# Humidifier.net
KiCad netlist of a schematic drawn in Altium Designer
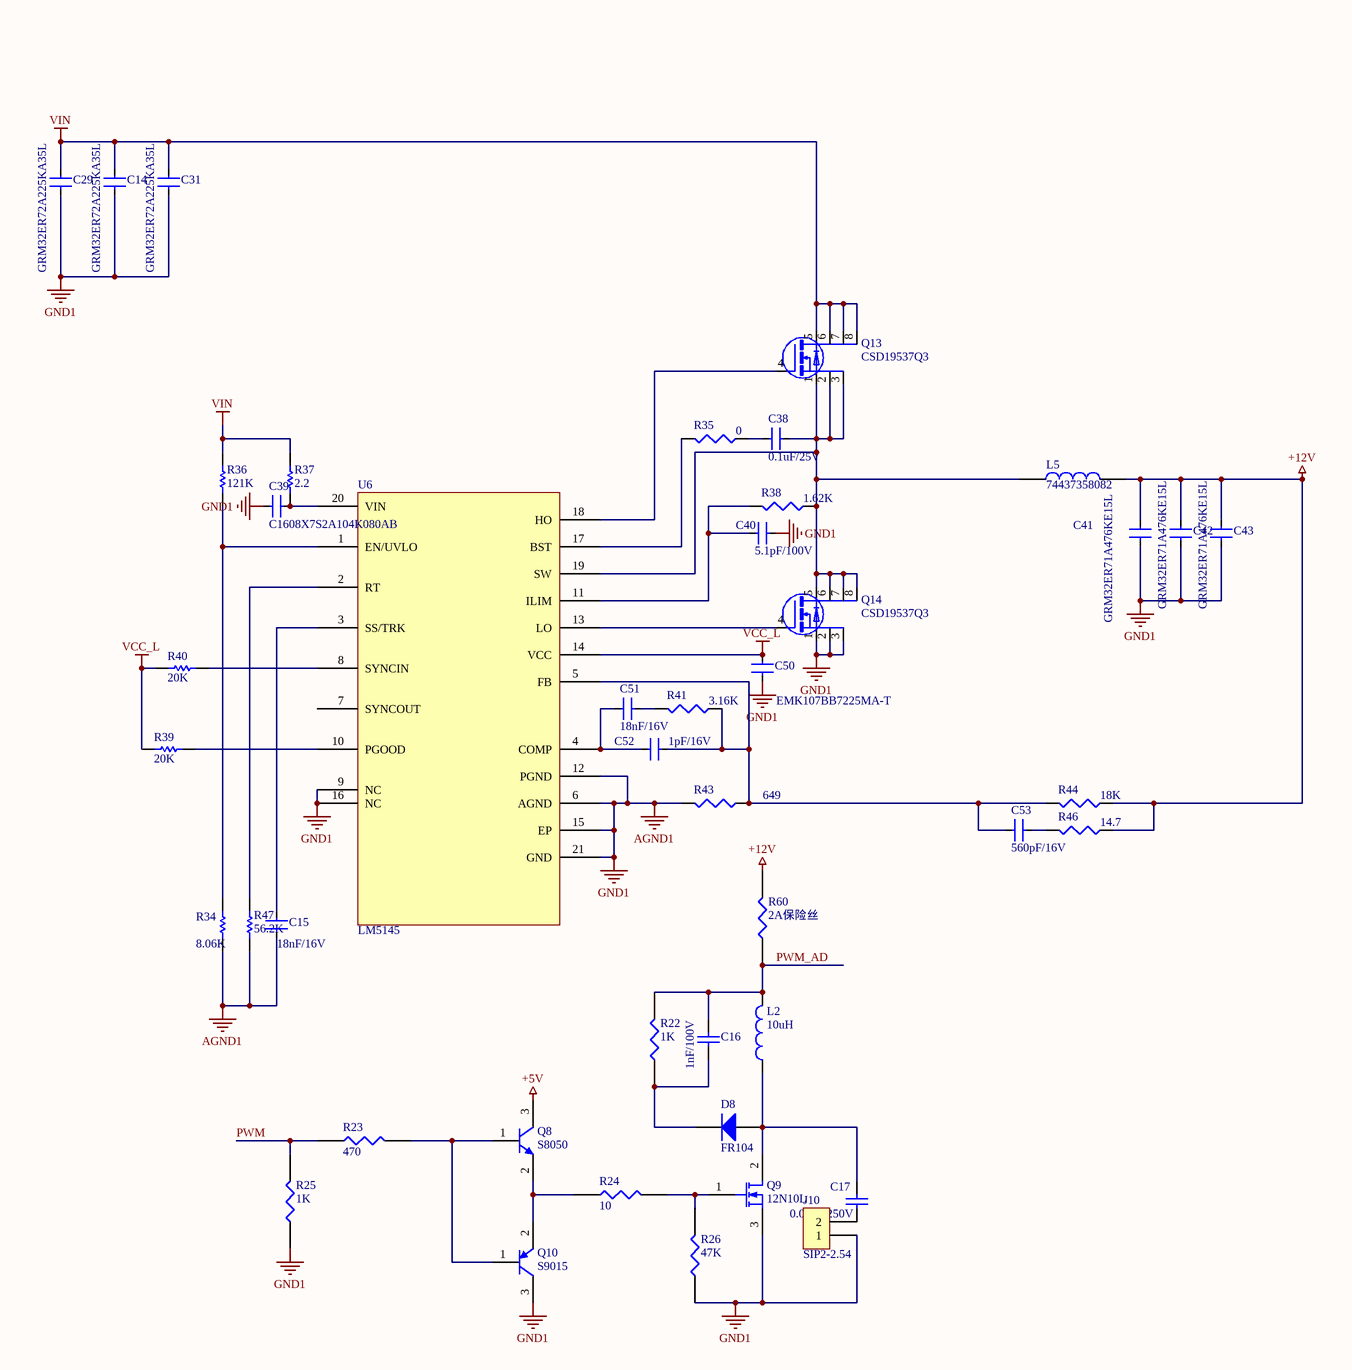
[diagram p0: Humidifier.SchDoc]

(export (version "E")
  (design (tool "Eeschema 10.0.6"))
  (components
    (comp (ref "C14")
      (value "GRM32ER72A225KA35L")
      (footprint "1210C")
      (description "CCX85-103")
      (libsource (lib "无极性电容") (part "0.01UF"))
    )
    (comp (ref "C15")
      (value "18nF/16V")
      (footprint "0603C")
      (description "CCX85-103")
      (libsource (lib "无极性电容") (part "0.01UF"))
    )
    (comp (ref "C16")
      (value "1nF/100V")
      (footprint "CAP_5MM")
      (description "Capacitor")
      (fields (field (name "PUBLISHER") "Altium Limited"))
      (libsource (lib "Miscellaneous Devices") (part "Cap"))
    )
    (comp (ref "C17")
      (value "0.047F/250V")
      (footprint "CAP_5MM")
      (description "Capacitor")
      (fields (field (name "PUBLISHER") "Altium Limited"))
      (libsource (lib "Miscellaneous Devices") (part "Cap"))
    )
    (comp (ref "C29")
      (value "GRM32ER72A225KA35L")
      (footprint "1210C")
      (description "CCX85-103")
      (libsource (lib "无极性电容") (part "0.01UF"))
    )
    (comp (ref "C31")
      (value "GRM32ER72A225KA35L")
      (footprint "1210C")
      (description "CCX85-103")
      (libsource (lib "无极性电容") (part "0.01UF"))
    )
    (comp (ref "C38")
      (value "0.1uF/25V")
      (footprint "0603C")
      (description "CCX85-103")
      (libsource (lib "无极性电容") (part "0.01UF"))
    )
    (comp (ref "C39")
      (value "C1608X7S2A104K080AB")
      (footprint "0603C")
      (description "CCX85-103")
      (libsource (lib "无极性电容") (part "0.01UF"))
    )
    (comp (ref "C40")
      (value "5.1pF/100V")
      (footprint "0603C")
      (description "CCX85-103")
      (libsource (lib "无极性电容") (part "0.01UF"))
    )
    (comp (ref "C41")
      (value "GRM32ER71A476KE15L")
      (footprint "1210C")
      (description "CCX85-103")
      (libsource (lib "无极性电容") (part "0.01UF"))
    )
    (comp (ref "C42")
      (value "GRM32ER71A476KE15L")
      (footprint "1210C")
      (description "CCX85-103")
      (libsource (lib "无极性电容") (part "0.01UF"))
    )
    (comp (ref "C43")
      (value "GRM32ER71A476KE15L")
      (footprint "1210C")
      (description "CCX85-103")
      (libsource (lib "无极性电容") (part "0.01UF"))
    )
    (comp (ref "C50")
      (value "EMK107BB7225MA-T")
      (footprint "0603C")
      (description "CCX85-103")
      (libsource (lib "无极性电容") (part "0.01UF"))
    )
    (comp (ref "C51")
      (value "18nF/16V")
      (footprint "0603C")
      (description "CCX85-103")
      (libsource (lib "无极性电容") (part "0.01UF"))
    )
    (comp (ref "C52")
      (value "1pF/16V")
      (footprint "0603C")
      (description "CCX85-103")
      (libsource (lib "无极性电容") (part "0.01UF"))
    )
    (comp (ref "C53")
      (value "560pF/16V")
      (footprint "0603C")
      (description "CCX85-103")
      (libsource (lib "无极性电容") (part "0.01UF"))
    )
    (comp (ref "D8")
      (value "FR104")
      (footprint "SMA")
      (description "Default Diode")
      (fields (field (name "PUBLISHER") "Altium Limited"))
      (libsource (lib "SM") (part "Diode_2"))
    )
    (comp (ref "J10")
      (value "SIP2-2.54")
      (footprint "SIP-2L")
      (description "CN-SIP2-2.54")
      (libsource (lib "接插件") (part "SIP2-2.54"))
    )
    (comp (ref "L2")
      (value "10uH")
      (footprint "6*8")
      (description "Inductor")
      (fields (field (name "PUBLISHER") "Altium Limited"))
      (libsource (lib "Miscellaneous Devices") (part "Inductor"))
    )
    (comp (ref "L5") (value "74437358082") (footprint "SRP1270-2R2M") (libsource (lib "*") (part "INDUCTOR")))
    (comp (ref "Q8")
      (value "S8050")
      (footprint "SOT23-3")
      (description "NPN Bipolar Transistor")
      (fields (field (name "PUBLISHER") "Altium Limited"))
      (libsource (lib "Miscellaneous Devices") (part "NPN"))
    )
    (comp (ref "Q9")
      (value "12N10L")
      (footprint "TO230P973X238-3N")
      (description "N-Channel MOSFET")
      (fields (field (name "PUBLISHER") "Altium Limited"))
      (libsource (lib "Miscellaneous Devices") (part "MOSFET-N"))
    )
    (comp (ref "Q10")
      (value "S9015")
      (footprint "SOT23-3")
      (description "PNP Bipolar Transistor")
      (fields (field (name "PUBLISHER") "Altium Limited"))
      (libsource (lib "Miscellaneous Devices") (part "PNP"))
    )
    (comp (ref "Q13")
      (value "CSD19537Q3")
      (footprint "PowerPAK SO-8")
      (description "Si4004DY")
      (libsource (lib "Schlib_20110825") (part "Si4004DY"))
    )
    (comp (ref "Q14")
      (value "CSD19537Q3")
      (footprint "PowerPAK SO-8")
      (description "Si4004DY")
      (libsource (lib "Schlib_20110825") (part "Si4004DY"))
    )
    (comp (ref "R22") (value "1K") (footprint "0805R") (libsource (lib "其他电阻") (part "RES1")))
    (comp (ref "R23") (value "470") (footprint "0805R") (libsource (lib "其他电阻") (part "RES1")))
    (comp (ref "R24") (value "10") (footprint "0805R") (libsource (lib "其他电阻") (part "RES1")))
    (comp (ref "R25") (value "1K") (footprint "0805R") (libsource (lib "其他电阻") (part "RES1")))
    (comp (ref "R26") (value "47K") (footprint "0805R") (libsource (lib "其他电阻") (part "RES1")))
    (comp (ref "R34")
      (value "8.06K")
      (footprint "0603R")
      (description "Semiconductor Resistor")
      (fields (field (name "PUBLISHER") "Altium Limited"))
      (libsource (lib "Miscellaneous Devices") (part "Res Semi"))
    )
    (comp (ref "R35")
      (value "0")
      (footprint "0603R")
      (description "Resistor")
      (fields (field (name "PUBLISHER") "Altium Limited"))
      (libsource (lib "SM") (part "Res3"))
    )
    (comp (ref "R36")
      (value "121K")
      (footprint "0805R")
      (description "Semiconductor Resistor")
      (fields (field (name "PUBLISHER") "Altium Limited"))
      (libsource (lib "Miscellaneous Devices") (part "Res Semi"))
    )
    (comp (ref "R37")
      (value "2.2")
      (footprint "0603R")
      (description "Semiconductor Resistor")
      (fields (field (name "PUBLISHER") "Altium Limited"))
      (libsource (lib "Miscellaneous Devices") (part "Res Semi"))
    )
    (comp (ref "R38")
      (value "1.62K")
      (footprint "0603R")
      (description "Resistor")
      (fields (field (name "PUBLISHER") "Altium Limited"))
      (libsource (lib "SM") (part "Res3"))
    )
    (comp (ref "R39")
      (value "20K")
      (footprint "0603R")
      (description "Semiconductor Resistor")
      (fields (field (name "PUBLISHER") "Altium Limited"))
      (libsource (lib "Miscellaneous Devices") (part "Res Semi"))
    )
    (comp (ref "R40")
      (value "20K")
      (footprint "0603R")
      (description "Semiconductor Resistor")
      (fields (field (name "PUBLISHER") "Altium Limited"))
      (libsource (lib "Miscellaneous Devices") (part "Res Semi"))
    )
    (comp (ref "R41")
      (value "3.16K")
      (footprint "0603R")
      (description "Resistor")
      (fields (field (name "PUBLISHER") "Altium Limited"))
      (libsource (lib "SM") (part "Res3"))
    )
    (comp (ref "R43")
      (value "649")
      (footprint "0603R")
      (description "Resistor")
      (fields (field (name "PUBLISHER") "Altium Limited"))
      (libsource (lib "SM") (part "Res3"))
    )
    (comp (ref "R44")
      (value "18K")
      (footprint "0603R")
      (description "Resistor")
      (fields (field (name "PUBLISHER") "Altium Limited"))
      (libsource (lib "SM") (part "Res3"))
    )
    (comp (ref "R46")
      (value "14.7")
      (footprint "0603R")
      (description "Resistor")
      (fields (field (name "PUBLISHER") "Altium Limited"))
      (libsource (lib "SM") (part "Res3"))
    )
    (comp (ref "R47")
      (value "56.2K")
      (footprint "0603R")
      (description "Semiconductor Resistor")
      (fields (field (name "PUBLISHER") "Altium Limited"))
      (libsource (lib "Miscellaneous Devices") (part "Res Semi"))
    )
    (comp (ref "R60") (value "2A保险丝") (footprint "0805R") (libsource (lib "其他电阻") (part "RES1")))
    (comp (ref "U6")
      (value "LM5145")
      (footprint "QFN050P600-8N")
      (libsource (lib "Schlib_20110825") (part "LM5145"))
    )
  )
  (nets
    (net (code "1") (name "+5V") (class "Default")
      (node (ref "Q8") (pin "3") (pinfunction "C_3") (pintype "passive"))
    )
    (net (code "2") (name "+12V") (class "Default")
      (node (ref "C41") (pin "1") (pinfunction "1_1") (pintype "passive"))
      (node (ref "C42") (pin "1") (pinfunction "1_1") (pintype "passive"))
      (node (ref "C43") (pin "1") (pinfunction "1_1") (pintype "passive"))
      (node (ref "L5") (pin "2") (pinfunction "2_2") (pintype "passive"))
      (node (ref "R44") (pin "1") (pinfunction "1_1") (pintype "passive"))
      (node (ref "R46") (pin "1") (pinfunction "1_1") (pintype "passive"))
      (node (ref "R60") (pin "2") (pinfunction "2_2") (pintype "passive"))
    )
    (net (code "3") (name "/PWM") (class "Default")
      (node (ref "R23") (pin "1") (pinfunction "1_1") (pintype "passive"))
      (node (ref "R25") (pin "2") (pinfunction "2_2") (pintype "passive"))
    )
    (net (code "4") (name "/PWM_AD") (class "Default")
      (node (ref "C16") (pin "2") (pinfunction "2_2") (pintype "passive"))
      (node (ref "L2") (pin "2") (pinfunction "2_2") (pintype "passive"))
      (node (ref "R22") (pin "2") (pinfunction "2_2") (pintype "passive"))
      (node (ref "R60") (pin "1") (pinfunction "1_1") (pintype "passive"))
    )
    (net (code "5") (name "AGND1") (class "Default")
      (node (ref "C14") (pin "2") (pinfunction "2_2") (pintype "passive"))
      (node (ref "C15") (pin "2") (pinfunction "2_2") (pintype "passive"))
      (node (ref "C29") (pin "2") (pinfunction "2_2") (pintype "passive"))
      (node (ref "C31") (pin "2") (pinfunction "2_2") (pintype "passive"))
      (node (ref "C39") (pin "1") (pinfunction "1_1") (pintype "passive"))
      (node (ref "C40") (pin "1") (pinfunction "1_1") (pintype "passive"))
      (node (ref "C41") (pin "2") (pinfunction "2_2") (pintype "passive"))
      (node (ref "C42") (pin "2") (pinfunction "2_2") (pintype "passive"))
      (node (ref "C43") (pin "2") (pinfunction "2_2") (pintype "passive"))
      (node (ref "C50") (pin "2") (pinfunction "2_2") (pintype "passive"))
      (node (ref "J10") (pin "1") (pinfunction "1_1") (pintype "passive"))
      (node (ref "Q10") (pin "3") (pinfunction "C_3") (pintype "passive"))
      (node (ref "Q14") (pin "1") (pinfunction "S_1") (pintype "passive"))
      (node (ref "Q14") (pin "2") (pinfunction "S_2") (pintype "passive"))
      (node (ref "Q14") (pin "3") (pinfunction "S_3") (pintype "passive"))
      (node (ref "Q9") (pin "3") (pinfunction "S_3") (pintype "passive"))
      (node (ref "R25") (pin "1") (pinfunction "1_1") (pintype "passive"))
      (node (ref "R26") (pin "1") (pinfunction "1_1") (pintype "passive"))
      (node (ref "R34") (pin "1") (pinfunction "1_1") (pintype "passive"))
      (node (ref "R43") (pin "2") (pinfunction "2_2") (pintype "passive"))
      (node (ref "R47") (pin "1") (pinfunction "1_1") (pintype "passive"))
      (node (ref "U6") (pin "12") (pinfunction "PGND_12") (pintype "passive"))
      (node (ref "U6") (pin "15") (pinfunction "EP_15") (pintype "passive"))
      (node (ref "U6") (pin "16") (pinfunction "NC_16") (pintype "passive"))
      (node (ref "U6") (pin "21") (pinfunction "GND_21") (pintype "passive"))
      (node (ref "U6") (pin "6") (pinfunction "AGND_6") (pintype "passive"))
      (node (ref "U6") (pin "9") (pinfunction "NC_9") (pintype "passive"))
    )
    (net (code "6") (name "Net-(C17-Pad1)") (class "Default")
      (node (ref "C17") (pin "1") (pinfunction "1_1") (pintype "passive"))
      (node (ref "J10") (pin "2") (pinfunction "2_2") (pintype "passive"))
    )
    (net (code "7") (name "Net-(C38-Pad1)") (class "Default")
      (node (ref "C38") (pin "1") (pinfunction "1_1") (pintype "passive"))
      (node (ref "R35") (pin "1") (pinfunction "1_1") (pintype "passive"))
    )
    (net (code "8") (name "Net-(C51-Pad2)") (class "Default")
      (node (ref "C51") (pin "2") (pinfunction "2_2") (pintype "passive"))
      (node (ref "R41") (pin "2") (pinfunction "2_2") (pintype "passive"))
    )
    (net (code "9") (name "Net-(C53-Pad2)") (class "Default")
      (node (ref "C53") (pin "2") (pinfunction "2_2") (pintype "passive"))
      (node (ref "R46") (pin "2") (pinfunction "2_2") (pintype "passive"))
    )
    (net (code "10") (name "Net-(D8-A)") (class "Default")
      (node (ref "C17") (pin "2") (pinfunction "2_2") (pintype "passive"))
      (node (ref "D8") (pin "1") (pinfunction "A_1") (pintype "passive"))
      (node (ref "L2") (pin "1") (pinfunction "1_1") (pintype "passive"))
      (node (ref "Q9") (pin "2") (pinfunction "D_2") (pintype "passive"))
    )
    (net (code "11") (name "Net-(D8-K)") (class "Default")
      (node (ref "C16") (pin "1") (pinfunction "1_1") (pintype "passive"))
      (node (ref "D8") (pin "2") (pinfunction "K_2") (pintype "passive"))
      (node (ref "R22") (pin "1") (pinfunction "1_1") (pintype "passive"))
    )
    (net (code "12") (name "Net-(Q9-G)") (class "Default")
      (node (ref "Q9") (pin "1") (pinfunction "G_1") (pintype "passive"))
      (node (ref "R24") (pin "2") (pinfunction "2_2") (pintype "passive"))
      (node (ref "R26") (pin "2") (pinfunction "2_2") (pintype "passive"))
    )
    (net (code "13") (name "Net-(Q10-B)") (class "Default")
      (node (ref "Q10") (pin "1") (pinfunction "B_1") (pintype "passive"))
      (node (ref "Q8") (pin "1") (pinfunction "B_1") (pintype "passive"))
      (node (ref "R23") (pin "2") (pinfunction "2_2") (pintype "passive"))
    )
    (net (code "14") (name "Net-(Q10-E)") (class "Default")
      (node (ref "Q10") (pin "2") (pinfunction "E_2") (pintype "passive"))
      (node (ref "Q8") (pin "2") (pinfunction "E_2") (pintype "passive"))
      (node (ref "R24") (pin "1") (pinfunction "1_1") (pintype "passive"))
    )
    (net (code "15") (name "Net-(Q13-G)") (class "Default")
      (node (ref "Q13") (pin "4") (pinfunction "G_4") (pintype "passive"))
      (node (ref "U6") (pin "18") (pinfunction "HO_18") (pintype "passive"))
    )
    (net (code "16") (name "Net-(Q14-G)") (class "Default")
      (node (ref "Q14") (pin "4") (pinfunction "G_4") (pintype "passive"))
      (node (ref "U6") (pin "13") (pinfunction "LO_13") (pintype "passive"))
    )
    (net (code "17") (name "Net-(U6-BST)") (class "Default")
      (node (ref "R35") (pin "2") (pinfunction "2_2") (pintype "passive"))
      (node (ref "U6") (pin "17") (pinfunction "BST_17") (pintype "passive"))
    )
    (net (code "18") (name "Net-(U6-COMP)") (class "Default")
      (node (ref "C51") (pin "1") (pinfunction "1_1") (pintype "passive"))
      (node (ref "C52") (pin "1") (pinfunction "1_1") (pintype "passive"))
      (node (ref "U6") (pin "4") (pinfunction "COMP_4") (pintype "passive"))
    )
    (net (code "19") (name "Net-(U6-EN{slash}UVLO)") (class "Default")
      (node (ref "R34") (pin "2") (pinfunction "2_2") (pintype "passive"))
      (node (ref "R36") (pin "1") (pinfunction "1_1") (pintype "passive"))
      (node (ref "U6") (pin "1") (pinfunction "EN/UVLO_1") (pintype "passive"))
    )
    (net (code "20") (name "Net-(U6-FB)") (class "Default")
      (node (ref "C52") (pin "2") (pinfunction "2_2") (pintype "passive"))
      (node (ref "C53") (pin "1") (pinfunction "1_1") (pintype "passive"))
      (node (ref "R41") (pin "1") (pinfunction "1_1") (pintype "passive"))
      (node (ref "R43") (pin "1") (pinfunction "1_1") (pintype "passive"))
      (node (ref "R44") (pin "2") (pinfunction "2_2") (pintype "passive"))
      (node (ref "U6") (pin "5") (pinfunction "FB_5") (pintype "passive"))
    )
    (net (code "21") (name "Net-(U6-ILIM)") (class "Default")
      (node (ref "C40") (pin "2") (pinfunction "2_2") (pintype "passive"))
      (node (ref "R38") (pin "2") (pinfunction "2_2") (pintype "passive"))
      (node (ref "U6") (pin "11") (pinfunction "ILIM_11") (pintype "passive"))
    )
    (net (code "22") (name "Net-(U6-PGOOD)") (class "Default")
      (node (ref "R39") (pin "1") (pinfunction "1_1") (pintype "passive"))
      (node (ref "U6") (pin "10") (pinfunction "PGOOD_10") (pintype "passive"))
    )
    (net (code "23") (name "Net-(U6-RT)") (class "Default")
      (node (ref "R47") (pin "2") (pinfunction "2_2") (pintype "passive"))
      (node (ref "U6") (pin "2") (pinfunction "RT_2") (pintype "passive"))
    )
    (net (code "24") (name "Net-(U6-SS{slash}TRK)") (class "Default")
      (node (ref "C15") (pin "1") (pinfunction "1_1") (pintype "passive"))
      (node (ref "U6") (pin "3") (pinfunction "SS/TRK_3") (pintype "passive"))
    )
    (net (code "25") (name "Net-(U6-SW)") (class "Default")
      (node (ref "C38") (pin "2") (pinfunction "2_2") (pintype "passive"))
      (node (ref "L5") (pin "1") (pinfunction "1_1") (pintype "passive"))
      (node (ref "Q13") (pin "1") (pinfunction "S_1") (pintype "passive"))
      (node (ref "Q13") (pin "2") (pinfunction "S_2") (pintype "passive"))
      (node (ref "Q13") (pin "3") (pinfunction "S_3") (pintype "passive"))
      (node (ref "Q14") (pin "5") (pinfunction "D_5") (pintype "passive"))
      (node (ref "Q14") (pin "6") (pinfunction "D_6") (pintype "passive"))
      (node (ref "Q14") (pin "7") (pinfunction "D_7") (pintype "passive"))
      (node (ref "Q14") (pin "8") (pinfunction "D_8") (pintype "passive"))
      (node (ref "R38") (pin "1") (pinfunction "1_1") (pintype "passive"))
      (node (ref "U6") (pin "19") (pinfunction "SW_19") (pintype "passive"))
    )
    (net (code "26") (name "Net-(U6-SYNCIN)") (class "Default")
      (node (ref "R40") (pin "1") (pinfunction "1_1") (pintype "passive"))
      (node (ref "U6") (pin "8") (pinfunction "SYNCIN_8") (pintype "passive"))
    )
    (net (code "27") (name "Net-(U6-VIN)") (class "Default")
      (node (ref "C39") (pin "2") (pinfunction "2_2") (pintype "passive"))
      (node (ref "R37") (pin "2") (pinfunction "2_2") (pintype "passive"))
      (node (ref "U6") (pin "20") (pinfunction "VIN_20") (pintype "passive"))
    )
    (net (code "28") (name "VCC_L") (class "Default")
      (node (ref "C50") (pin "1") (pinfunction "1_1") (pintype "passive"))
      (node (ref "R39") (pin "2") (pinfunction "2_2") (pintype "passive"))
      (node (ref "R40") (pin "2") (pinfunction "2_2") (pintype "passive"))
      (node (ref "U6") (pin "14") (pinfunction "VCC_14") (pintype "passive"))
    )
    (net (code "29") (name "VIN") (class "Default")
      (node (ref "C14") (pin "1") (pinfunction "1_1") (pintype "passive"))
      (node (ref "C29") (pin "1") (pinfunction "1_1") (pintype "passive"))
      (node (ref "C31") (pin "1") (pinfunction "1_1") (pintype "passive"))
      (node (ref "Q13") (pin "5") (pinfunction "D_5") (pintype "passive"))
      (node (ref "Q13") (pin "6") (pinfunction "D_6") (pintype "passive"))
      (node (ref "Q13") (pin "7") (pinfunction "D_7") (pintype "passive"))
      (node (ref "Q13") (pin "8") (pinfunction "D_8") (pintype "passive"))
      (node (ref "R36") (pin "2") (pinfunction "2_2") (pintype "passive"))
      (node (ref "R37") (pin "1") (pinfunction "1_1") (pintype "passive"))
    )
    (net (code "30") (name "unconnected-(U6-SYNCOUT-Pad7)") (class "Default")
      (node (ref "U6") (pin "7") (pinfunction "SYNCOUT_7") (pintype "passive"))
    )
  )
)
